# LEDs_Buttons.net
KiCad netlist of a schematic drawn in Altium Designer
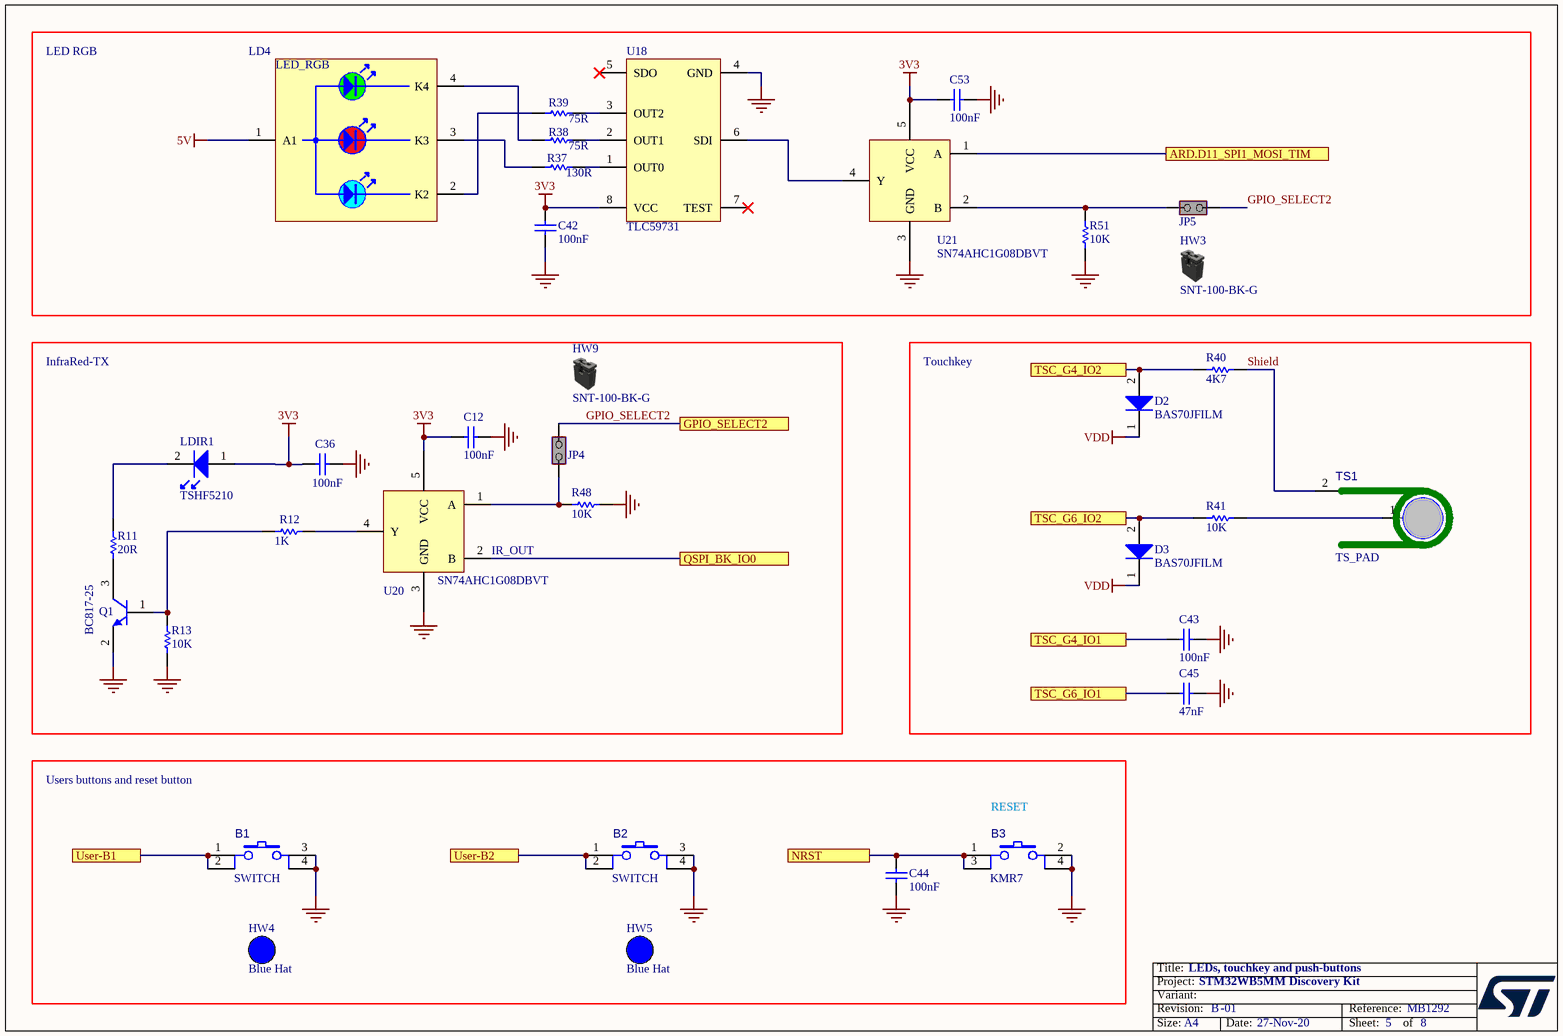
[diagram p0: LEDs_Buttons.SchDoc]

(export (version "E")
  (design (tool "Eeschema 10.0.6"))
  (components
    (comp (ref "B1")
      (value "SWITCH")
      (footprint "SWI_WEALTHMETAL_TD-0341_4P_BLUE")
      (description "Non-Open Push-Button 0.1A 24V")
      (fields
        (field (name "INTERNAL_PART_NUMBER") "MCD-00002")
        (field (name "MANUFACTURER_PART_NUMBER") "TD-0341")
      )
      (libsource (lib "MCD_PARTS_database") (part "SW-PUSH-CMS"))
    )
    (comp (ref "B2")
      (value "SWITCH")
      (footprint "SWI_WEALTHMETAL_TD-0341_4P_BLUE")
      (description "Non-Open Push-Button 0.1A 24V")
      (fields
        (field (name "INTERNAL_PART_NUMBER") "MCD-00002")
        (field (name "MANUFACTURER_PART_NUMBER") "TD-0341")
      )
      (libsource (lib "MCD_PARTS_database") (part "SW-PUSH-CMS"))
    )
    (comp (ref "B3")
      (value "KMR7")
      (footprint "SWI_C&K_KMR721NG-LFS")
      (description "Microminiature SMT Top, 2N, N.O., IP67")
      (fields
        (field (name "INTERNAL_PART_NUMBER") "MCD-01510")
        (field (name "MANUFACTURER_PART_NUMBER") "KMR721NG LFS")
      )
      (libsource (lib "MCD_PARTS_database") (part "SW-PUSH-CMS_KMR_NG"))
    )
    (comp (ref "C12")
      (value "100nF")
      (footprint "C0402")
      (description "Capacitor, MLCC, 100nF, 16V, X7R, +/-10%, 0402, T=0.5mm")
      (fields
        (field (name "INTERNAL_PART_NUMBER") "MCD-00006")
        (field (name "MANUFACTURER_PART_NUMBER") "CC0402KRX7R7BB104")
      )
      (libsource (lib "MCD_PARTS_database") (part "Capacitor"))
    )
    (comp (ref "C36")
      (value "100nF")
      (footprint "C0402")
      (description "Capacitor, MLCC, 100nF, 16V, X7R, +/-10%, 0402, T=0.5mm")
      (fields
        (field (name "INTERNAL_PART_NUMBER") "MCD-00006")
        (field (name "MANUFACTURER_PART_NUMBER") "CC0402KRX7R7BB104")
      )
      (libsource (lib "MCD_PARTS_database") (part "Capacitor"))
    )
    (comp (ref "C42")
      (value "100nF")
      (footprint "C0402")
      (description "Capacitor, MLCC, 100nF, 16V, X7R, +/-10%, 0402, T=0.5mm")
      (fields
        (field (name "INTERNAL_PART_NUMBER") "MCD-00006")
        (field (name "MANUFACTURER_PART_NUMBER") "CC0402KRX7R7BB104")
      )
      (libsource (lib "MCD_PARTS_database") (part "Capacitor"))
    )
    (comp (ref "C43")
      (value "100nF")
      (footprint "C1206_H1P6")
      (description "Capacitor, COG, 100nF, 25V , 1206, 5%")
      (fields
        (field (name "INTERNAL_PART_NUMBER") "MCD-02039")
        (field (name "MANUFACTURER_PART_NUMBER") "C1206X104J3GACTU")
      )
      (libsource (lib "MCD_PARTS_database") (part "Capacitor"))
    )
    (comp (ref "C44")
      (value "100nF")
      (footprint "C0402")
      (description "Capacitor, MLCC, 100nF, 16V, X7R, +/-10%, 0402, T=0.5mm")
      (fields
        (field (name "INTERNAL_PART_NUMBER") "MCD-00006")
        (field (name "MANUFACTURER_PART_NUMBER") "CC0402KRX7R7BB104")
      )
      (libsource (lib "MCD_PARTS_database") (part "Capacitor"))
    )
    (comp (ref "C45")
      (value "47nF")
      (footprint "C0805_KEMET_IPC-7351_DENSITY-LEVEL-B_H1P25")
      (description "Capacitor, COG, 47nF, 25V , 0805, 5%")
      (fields
        (field (name "INTERNAL_PART_NUMBER") "MCD-02040")
        (field (name "MANUFACTURER_PART_NUMBER") "C0805C473J3GACTU")
      )
      (libsource (lib "MCD_PARTS_database") (part "Capacitor"))
    )
    (comp (ref "C53")
      (value "100nF")
      (footprint "C0402")
      (description "Capacitor, MLCC, 100nF, 16V, X7R, +/-10%, 0402, T=0.5mm")
      (fields
        (field (name "INTERNAL_PART_NUMBER") "MCD-00006")
        (field (name "MANUFACTURER_PART_NUMBER") "CC0402KRX7R7BB104")
      )
      (libsource (lib "MCD_PARTS_database") (part "Capacitor"))
    )
    (comp (ref "D2")
      (value "BAS70JFILM")
      (footprint "DIO_SOD323_1K_2A")
      (description "ultrafast and RF switching diode, VF = 0.41 V @ IF = 1mA; VR = 70V;")
      (fields
        (field (name "INTERNAL_PART_NUMBER") "MCD-01880")
        (field (name "MANUFACTURER") "STMICROELECTRONICS")
      )
      (libsource (lib "MCD_PARTS_database") (part "DIODE_1K_2A"))
    )
    (comp (ref "D3")
      (value "BAS70JFILM")
      (footprint "DIO_SOD323_1K_2A")
      (description "ultrafast and RF switching diode, VF = 0.41 V @ IF = 1mA; VR = 70V;")
      (fields
        (field (name "INTERNAL_PART_NUMBER") "MCD-01880")
        (field (name "MANUFACTURER") "STMICROELECTRONICS")
      )
      (libsource (lib "MCD_PARTS_database") (part "DIODE_1K_2A"))
    )
    (comp (ref "HW3")
      (value "SNT-100-BK-G")
      (description "SHUNT 2.54mm BLACK")
      (fields (field (name "INTERNAL_PART_NUMBER") "MCD-00043") (field (name "MANUFACTURER") "SAMTEC"))
      (libsource (lib "MCD_PARTS_database") (part "Shunt Black 2.54mm"))
    )
    (comp (ref "HW4")
      (value "Blue Hat")
      (description "switch hat,blue,KTSC-62B")
      (fields
        (field (name "INTERNAL_PART_NUMBER") "MCD-02136")
        (field (name "MANUFACTURER_PART_NUMBER") "AKTSC62B")
      )
      (libsource (lib "MCD_PARTS_database") (part "BUTTON_HAT_BLUE"))
    )
    (comp (ref "HW5")
      (value "Blue Hat")
      (description "switch hat,blue,KTSC-62B")
      (fields
        (field (name "INTERNAL_PART_NUMBER") "MCD-02136")
        (field (name "MANUFACTURER_PART_NUMBER") "AKTSC62B")
      )
      (libsource (lib "MCD_PARTS_database") (part "BUTTON_HAT_BLUE"))
    )
    (comp (ref "HW9")
      (value "SNT-100-BK-G")
      (description "SHUNT 2.54mm BLACK")
      (fields (field (name "INTERNAL_PART_NUMBER") "MCD-00043") (field (name "MANUFACTURER") "SAMTEC"))
      (libsource (lib "MCD_PARTS_database") (part "Shunt Black 2.54mm"))
    )
    (comp (ref "JP4")
      (value "Jumper_Header 2x1 Fitted")
      (footprint "CON_SAMTEC_TSW-102-07-G-S")
      (description "Header, 2x1, 2,54mm, VR, TH, Height 5.84mm/2.54mm - Shunt Fitted by default")
      (fields
        (field (name "INTERNAL_PART_NUMBER") "MCD-01904")
        (field (name "MANUFACTURER_PART_NUMBER") "TSW-102-07-G-S")
      )
      (libsource (lib "MCD_PARTS_database") (part "Jumper_Header 2x1 Fitted"))
    )
    (comp (ref "JP5")
      (value "Jumper_Header 2x1 Fitted")
      (footprint "CON_SAMTEC_TSW-102-07-G-S")
      (description "Header, 2x1, 2,54mm, VR, TH, Height 5.84mm/2.54mm - Shunt Fitted by default")
      (fields
        (field (name "INTERNAL_PART_NUMBER") "MCD-01904")
        (field (name "MANUFACTURER_PART_NUMBER") "TSW-102-07-G-S")
      )
      (libsource (lib "") (part "Jumper_Header 2x1 Fitted_1"))
    )
    (comp (ref "LD4")
      (value "LED_RGB")
      (footprint "LED_TRI-RGB_WURTH_150141M173100")
      (description "LED, RGB 2,8x3,2mm")
      (fields
        (field (name "INTERNAL_PART_NUMBER") "MCD-02035")
        (field (name "MANUFACTURER_PART_NUMBER") "150141M173100")
      )
      (libsource (lib "MCD_PARTS_database") (part "LED_RGB"))
    )
    (comp (ref "LDIR1")
      (value "TSHF5210")
      (footprint "LED_INFRARED_VISHAY_TSHF5210_IN-MODE-SMT_BOARD-EDGE_1A2K_P254")
      (description "Diode infrared, 890nm emitting, T-1 3/4, 35,5mmx2.54mm")
      (fields (field (name "INTERNAL_PART_NUMBER") "MCD-02137") (field (name "MANUFACTURER") "VISHAY"))
      (libsource (lib "MCD_PARTS_database") (part "TSHF5210"))
    )
    (comp (ref "Q1")
      (value "BC817-25")
      (footprint "NPN_SOT23")
      (description "Transistor Bipolar NPN, 45V, 500mA, 100MHz, 300mW, SOT23-3")
      (fields
        (field (name "INTERNAL_PART_NUMBER") "MCD-01385")
        (field (name "MANUFACTURER_PART_NUMBER") "BC817-25LT3G")
      )
      (libsource (lib "MCD_PARTS_database") (part "9013-SOT23"))
    )
    (comp (ref "R11")
      (value "20R")
      (footprint "R0603")
      (description "Resistor,20R,0603,1%,1/10W")
      (fields
        (field (name "INTERNAL_PART_NUMBER") "MCD-00345")
        (field (name "MANUFACTURER_PART_NUMBER") "RC0603FR-0720RL")
      )
      (libsource (lib "MCD_PARTS_database") (part "Resistor"))
    )
    (comp (ref "R12")
      (value "1K")
      (footprint "R0402")
      (description "Resistor,1K,0402,1%,1/16W")
      (fields
        (field (name "INTERNAL_PART_NUMBER") "MCD-00061")
        (field (name "MANUFACTURER_PART_NUMBER") "RC0402FR-071KL")
      )
      (libsource (lib "MCD_PARTS_database") (part "Resistor"))
    )
    (comp (ref "R13")
      (value "10K")
      (footprint "R0402")
      (description "Resistor,10K,0402,1%,1/16W")
      (fields
        (field (name "INTERNAL_PART_NUMBER") "MCD-00053")
        (field (name "MANUFACTURER_PART_NUMBER") "RC0402FR-0710KL")
      )
      (libsource (lib "MCD_PARTS_database") (part "Resistor"))
    )
    (comp (ref "R37")
      (value "130R")
      (footprint "R0603")
      (description "Resistor,130R,0603,1%,1/10W")
      (fields
        (field (name "INTERNAL_PART_NUMBER") "MCD-00380")
        (field (name "MANUFACTURER_PART_NUMBER") "RC0603FR-07130RL")
      )
      (libsource (lib "MCD_PARTS_database") (part "Resistor"))
    )
    (comp (ref "R38")
      (value "75R")
      (footprint "R0603")
      (description "Resistor,75R,0603,1%,1/10W")
      (fields
        (field (name "INTERNAL_PART_NUMBER") "MCD-00516")
        (field (name "MANUFACTURER_PART_NUMBER") "RC0603FR-0775RL")
      )
      (libsource (lib "MCD_PARTS_database") (part "Resistor"))
    )
    (comp (ref "R39")
      (value "75R")
      (footprint "R0603")
      (description "Resistor,75R,0603,1%,1/10W")
      (fields
        (field (name "INTERNAL_PART_NUMBER") "MCD-00516")
        (field (name "MANUFACTURER_PART_NUMBER") "RC0603FR-0775RL")
      )
      (libsource (lib "MCD_PARTS_database") (part "Resistor"))
    )
    (comp (ref "R40")
      (value "4K7")
      (footprint "R0603")
      (description "Resistor,4K7,0603,1%,1/10W")
      (fields
        (field (name "INTERNAL_PART_NUMBER") "MCD-00219")
        (field (name "MANUFACTURER_PART_NUMBER") "RC0603FR-074K7L")
      )
      (libsource (lib "MCD_PARTS_database") (part "Resistor"))
    )
    (comp (ref "R41")
      (value "10K")
      (footprint "R0603")
      (description "Resistor,10K,0603,1%,1/10W")
      (fields
        (field (name "INTERNAL_PART_NUMBER") "MCD-00220")
        (field (name "MANUFACTURER_PART_NUMBER") "RC0603FR-0710KL")
      )
      (libsource (lib "MCD_PARTS_database") (part "Resistor"))
    )
    (comp (ref "R48")
      (value "10K")
      (footprint "R0402")
      (description "Resistor,10K,0402,1%,1/16W")
      (fields
        (field (name "INTERNAL_PART_NUMBER") "MCD-00053")
        (field (name "MANUFACTURER_PART_NUMBER") "RC0402FR-0710KL")
      )
      (libsource (lib "MCD_PARTS_database") (part "Resistor"))
    )
    (comp (ref "R51")
      (value "10K")
      (footprint "R0402")
      (description "Resistor,10K,0402,1%,1/16W")
      (fields
        (field (name "INTERNAL_PART_NUMBER") "MCD-00053")
        (field (name "MANUFACTURER_PART_NUMBER") "RC0402FR-0710KL")
      )
      (libsource (lib "MCD_PARTS_database") (part "Resistor"))
    )
    (comp (ref "TS1")
      (value "TS_PAD")
      (footprint "TSB_TOUCH-SENSING-BUTTON_TS-PAD-10_SHIELD-14_2")
      (description "-Touch Sensing button: diameter 10mm min,  active shield diameter 12mm min")
      (fields
        (field (name "INTERNAL_PART_NUMBER") "MCD-02082")
        (field (name "MANUFACTURER_PART_NUMBER") "Touch_sensing_Button")
      )
      (libsource (lib "MCD_PARTS_database") (part "TS_PAD"))
    )
    (comp (ref "U18")
      (value "TLC59731")
      (footprint "ICC_SOIC8_3P91X4P90_P127_H1P75")
      (description "LED, driver for PWM, 4.90 mm × 3.91 mm")
      (fields
        (field (name "INTERNAL_PART_NUMBER") "MCD-02033")
        (field (name "MANUFACTURER") "TEXAS INSTRUMENTS")
      )
      (libsource (lib "MCD_PARTS_database") (part "TLC59731"))
    )
    (comp (ref "U20")
      (value "SN74AHC1G08DBVT")
      (footprint "ICC_SOT23-5L_H1P45")
      (description "Logic AND Gate, 2.90 mm × 1.60 mm")
      (fields
        (field (name "INTERNAL_PART_NUMBER") "MCD-02053")
        (field (name "MANUFACTURER") "TEXAS INSTRUMENTS")
      )
      (libsource (lib "MCD_PARTS_database") (part "SN74AHC1G08DBVT"))
    )
    (comp (ref "U21")
      (value "SN74AHC1G08DBVT")
      (footprint "ICC_SOT23-5L_H1P45")
      (description "Logic AND Gate, 2.90 mm × 1.60 mm")
      (fields
        (field (name "INTERNAL_PART_NUMBER") "MCD-02053")
        (field (name "MANUFACTURER") "TEXAS INSTRUMENTS")
      )
      (libsource (lib "MCD_PARTS_database") (part "SN74AHC1G08DBVT"))
    )
  )
  (nets
    (net (code "1") (name "/ARD.D11_SPI1_MOSI_TIM") (class "Default")
      (node (ref "U21") (pin "1") (pinfunction "A_1") (pintype "passive"))
    )
    (net (code "2") (name "/GPIO_SELECT2") (class "Default")
      (node (ref "JP4") (pin "1") (pinfunction "COMMON_1") (pintype "passive"))
      (node (ref "JP5") (pin "2") (pinfunction "NO_2") (pintype "passive"))
    )
    (net (code "3") (name "/NRST") (class "Default")
      (node (ref "B3") (pin "1") (pinfunction "1_1") (pintype "passive"))
      (node (ref "B3") (pin "3") (pinfunction "3_3") (pintype "passive"))
      (node (ref "C44") (pin "1") (pinfunction "1_1") (pintype "passive"))
    )
    (net (code "4") (name "/QSPI_BK_IO0") (class "Default")
      (node (ref "U20") (pin "2") (pinfunction "B_2") (pintype "passive"))
    )
    (net (code "5") (name "/Shield") (class "Default")
      (node (ref "R40") (pin "2") (pinfunction "2_2") (pintype "passive"))
      (node (ref "TS1") (pin "2") (pinfunction "SHIELD_2") (pintype "passive"))
    )
    (net (code "6") (name "/TSC_G4_IO1") (class "Default")
      (node (ref "C43") (pin "2") (pinfunction "2_2") (pintype "passive"))
    )
    (net (code "7") (name "/TSC_G4_IO2") (class "Default")
      (node (ref "D2") (pin "2") (pinfunction "A_2") (pintype "passive"))
      (node (ref "R40") (pin "1") (pinfunction "1_1") (pintype "passive"))
    )
    (net (code "8") (name "/TSC_G6_IO1") (class "Default")
      (node (ref "C45") (pin "2") (pinfunction "2_2") (pintype "passive"))
    )
    (net (code "9") (name "/TSC_G6_IO2") (class "Default")
      (node (ref "D3") (pin "2") (pinfunction "A_2") (pintype "passive"))
      (node (ref "R41") (pin "1") (pinfunction "1_1") (pintype "passive"))
    )
    (net (code "10") (name "/User-B1") (class "Default")
      (node (ref "B1") (pin "1") (pinfunction "1_1") (pintype "passive"))
      (node (ref "B1") (pin "2") (pinfunction "2_2") (pintype "passive"))
    )
    (net (code "11") (name "/User-B2") (class "Default")
      (node (ref "B2") (pin "1") (pinfunction "1_1") (pintype "passive"))
      (node (ref "B2") (pin "2") (pinfunction "2_2") (pintype "passive"))
    )
    (net (code "12") (name "3V3") (class "Default")
      (node (ref "C12") (pin "2") (pinfunction "2_2") (pintype "passive"))
      (node (ref "C36") (pin "2") (pinfunction "2_2") (pintype "passive"))
      (node (ref "C42") (pin "2") (pinfunction "2_2") (pintype "passive"))
      (node (ref "C53") (pin "2") (pinfunction "2_2") (pintype "passive"))
      (node (ref "LDIR1") (pin "1") (pinfunction "A_1") (pintype "passive"))
      (node (ref "U18") (pin "8") (pinfunction "VCC_8") (pintype "passive"))
      (node (ref "U20") (pin "5") (pinfunction "VCC_5") (pintype "passive"))
      (node (ref "U21") (pin "5") (pinfunction "VCC_5") (pintype "passive"))
    )
    (net (code "13") (name "5V") (class "Default")
      (node (ref "LD4") (pin "1") (pinfunction "A1_1") (pintype "passive"))
    )
    (net (code "14") (name "GND") (class "Default")
      (node (ref "B1") (pin "3") (pinfunction "3_3") (pintype "passive"))
      (node (ref "B1") (pin "4") (pinfunction "4_4") (pintype "passive"))
      (node (ref "B2") (pin "3") (pinfunction "3_3") (pintype "passive"))
      (node (ref "B2") (pin "4") (pinfunction "4_4") (pintype "passive"))
      (node (ref "B3") (pin "2") (pinfunction "2_2") (pintype "passive"))
      (node (ref "B3") (pin "4") (pinfunction "4_4") (pintype "passive"))
      (node (ref "C12") (pin "1") (pinfunction "1_1") (pintype "passive"))
      (node (ref "C36") (pin "1") (pinfunction "1_1") (pintype "passive"))
      (node (ref "C42") (pin "1") (pinfunction "1_1") (pintype "passive"))
      (node (ref "C43") (pin "1") (pinfunction "1_1") (pintype "passive"))
      (node (ref "C44") (pin "2") (pinfunction "2_2") (pintype "passive"))
      (node (ref "C45") (pin "1") (pinfunction "1_1") (pintype "passive"))
      (node (ref "C53") (pin "1") (pinfunction "1_1") (pintype "passive"))
      (node (ref "Q1") (pin "2") (pinfunction "E_2") (pintype "passive"))
      (node (ref "R13") (pin "1") (pinfunction "1_1") (pintype "passive"))
      (node (ref "R48") (pin "2") (pinfunction "2_2") (pintype "passive"))
      (node (ref "R51") (pin "1") (pinfunction "1_1") (pintype "passive"))
      (node (ref "U18") (pin "4") (pinfunction "GND_4") (pintype "passive"))
      (node (ref "U20") (pin "3") (pinfunction "GND_3") (pintype "passive"))
      (node (ref "U21") (pin "3") (pinfunction "GND_3") (pintype "passive"))
    )
    (net (code "15") (name "Net-(JP4-NO)") (class "Default")
      (node (ref "JP4") (pin "2") (pinfunction "NO_2") (pintype "passive"))
      (node (ref "R48") (pin "1") (pinfunction "1_1") (pintype "passive"))
      (node (ref "U20") (pin "1") (pinfunction "A_1") (pintype "passive"))
    )
    (net (code "16") (name "Net-(JP5-COMMON)") (class "Default")
      (node (ref "JP5") (pin "1") (pinfunction "COMMON_1") (pintype "passive"))
      (node (ref "R51") (pin "2") (pinfunction "2_2") (pintype "passive"))
      (node (ref "U21") (pin "2") (pinfunction "B_2") (pintype "passive"))
    )
    (net (code "17") (name "Net-(LD4-K2)") (class "Default")
      (node (ref "LD4") (pin "2") (pinfunction "K2_2") (pintype "passive"))
      (node (ref "R39") (pin "1") (pinfunction "1_1") (pintype "passive"))
    )
    (net (code "18") (name "Net-(LD4-K3)") (class "Default")
      (node (ref "LD4") (pin "3") (pinfunction "K3_3") (pintype "passive"))
      (node (ref "R37") (pin "1") (pinfunction "1_1") (pintype "passive"))
    )
    (net (code "19") (name "Net-(LD4-K4)") (class "Default")
      (node (ref "LD4") (pin "4") (pinfunction "K4_4") (pintype "passive"))
      (node (ref "R38") (pin "1") (pinfunction "1_1") (pintype "passive"))
    )
    (net (code "20") (name "Net-(LDIR1-K)") (class "Default")
      (node (ref "LDIR1") (pin "2") (pinfunction "K_2") (pintype "passive"))
      (node (ref "R11") (pin "1") (pinfunction "1_1") (pintype "passive"))
    )
    (net (code "21") (name "Net-(Q1-B)") (class "Default")
      (node (ref "Q1") (pin "1") (pinfunction "B_1") (pintype "passive"))
      (node (ref "R12") (pin "1") (pinfunction "1_1") (pintype "passive"))
      (node (ref "R13") (pin "2") (pinfunction "2_2") (pintype "passive"))
    )
    (net (code "22") (name "Net-(Q1-C)") (class "Default")
      (node (ref "Q1") (pin "3") (pinfunction "C_3") (pintype "passive"))
      (node (ref "R11") (pin "2") (pinfunction "2_2") (pintype "passive"))
    )
    (net (code "23") (name "Net-(TS1-TKEY)") (class "Default")
      (node (ref "R41") (pin "2") (pinfunction "2_2") (pintype "passive"))
      (node (ref "TS1") (pin "1") (pinfunction "TKEY_1") (pintype "passive"))
    )
    (net (code "24") (name "Net-(U18-OUT0)") (class "Default")
      (node (ref "R37") (pin "2") (pinfunction "2_2") (pintype "passive"))
      (node (ref "U18") (pin "1") (pinfunction "OUT0_1") (pintype "passive"))
    )
    (net (code "25") (name "Net-(U18-OUT1)") (class "Default")
      (node (ref "R38") (pin "2") (pinfunction "2_2") (pintype "passive"))
      (node (ref "U18") (pin "2") (pinfunction "OUT1_2") (pintype "passive"))
    )
    (net (code "26") (name "Net-(U18-OUT2)") (class "Default")
      (node (ref "R39") (pin "2") (pinfunction "2_2") (pintype "passive"))
      (node (ref "U18") (pin "3") (pinfunction "OUT2_3") (pintype "passive"))
    )
    (net (code "27") (name "Net-(U18-SDI)") (class "Default")
      (node (ref "U18") (pin "6") (pinfunction "SDI_6") (pintype "passive"))
      (node (ref "U21") (pin "4") (pinfunction "Y_4") (pintype "passive"))
    )
    (net (code "28") (name "Net-(U20-Y)") (class "Default")
      (node (ref "R12") (pin "2") (pinfunction "2_2") (pintype "passive"))
      (node (ref "U20") (pin "4") (pinfunction "Y_4") (pintype "passive"))
    )
    (net (code "29") (name "VDD") (class "Default")
      (node (ref "D2") (pin "1") (pinfunction "K_1") (pintype "passive"))
      (node (ref "D3") (pin "1") (pinfunction "K_1") (pintype "passive"))
    )
    (net (code "30") (name "unconnected-(U18-SDO-Pad5)") (class "Default")
      (node (ref "U18") (pin "5") (pinfunction "SDO_5") (pintype "passive+no_connect"))
    )
    (net (code "31") (name "unconnected-(U18-TEST-Pad7)") (class "Default")
      (node (ref "U18") (pin "7") (pinfunction "TEST_7") (pintype "passive+no_connect"))
    )
  )
)
